# carcomputer_bottom2.net
KiCad netlist of a schematic drawn in EAGLE
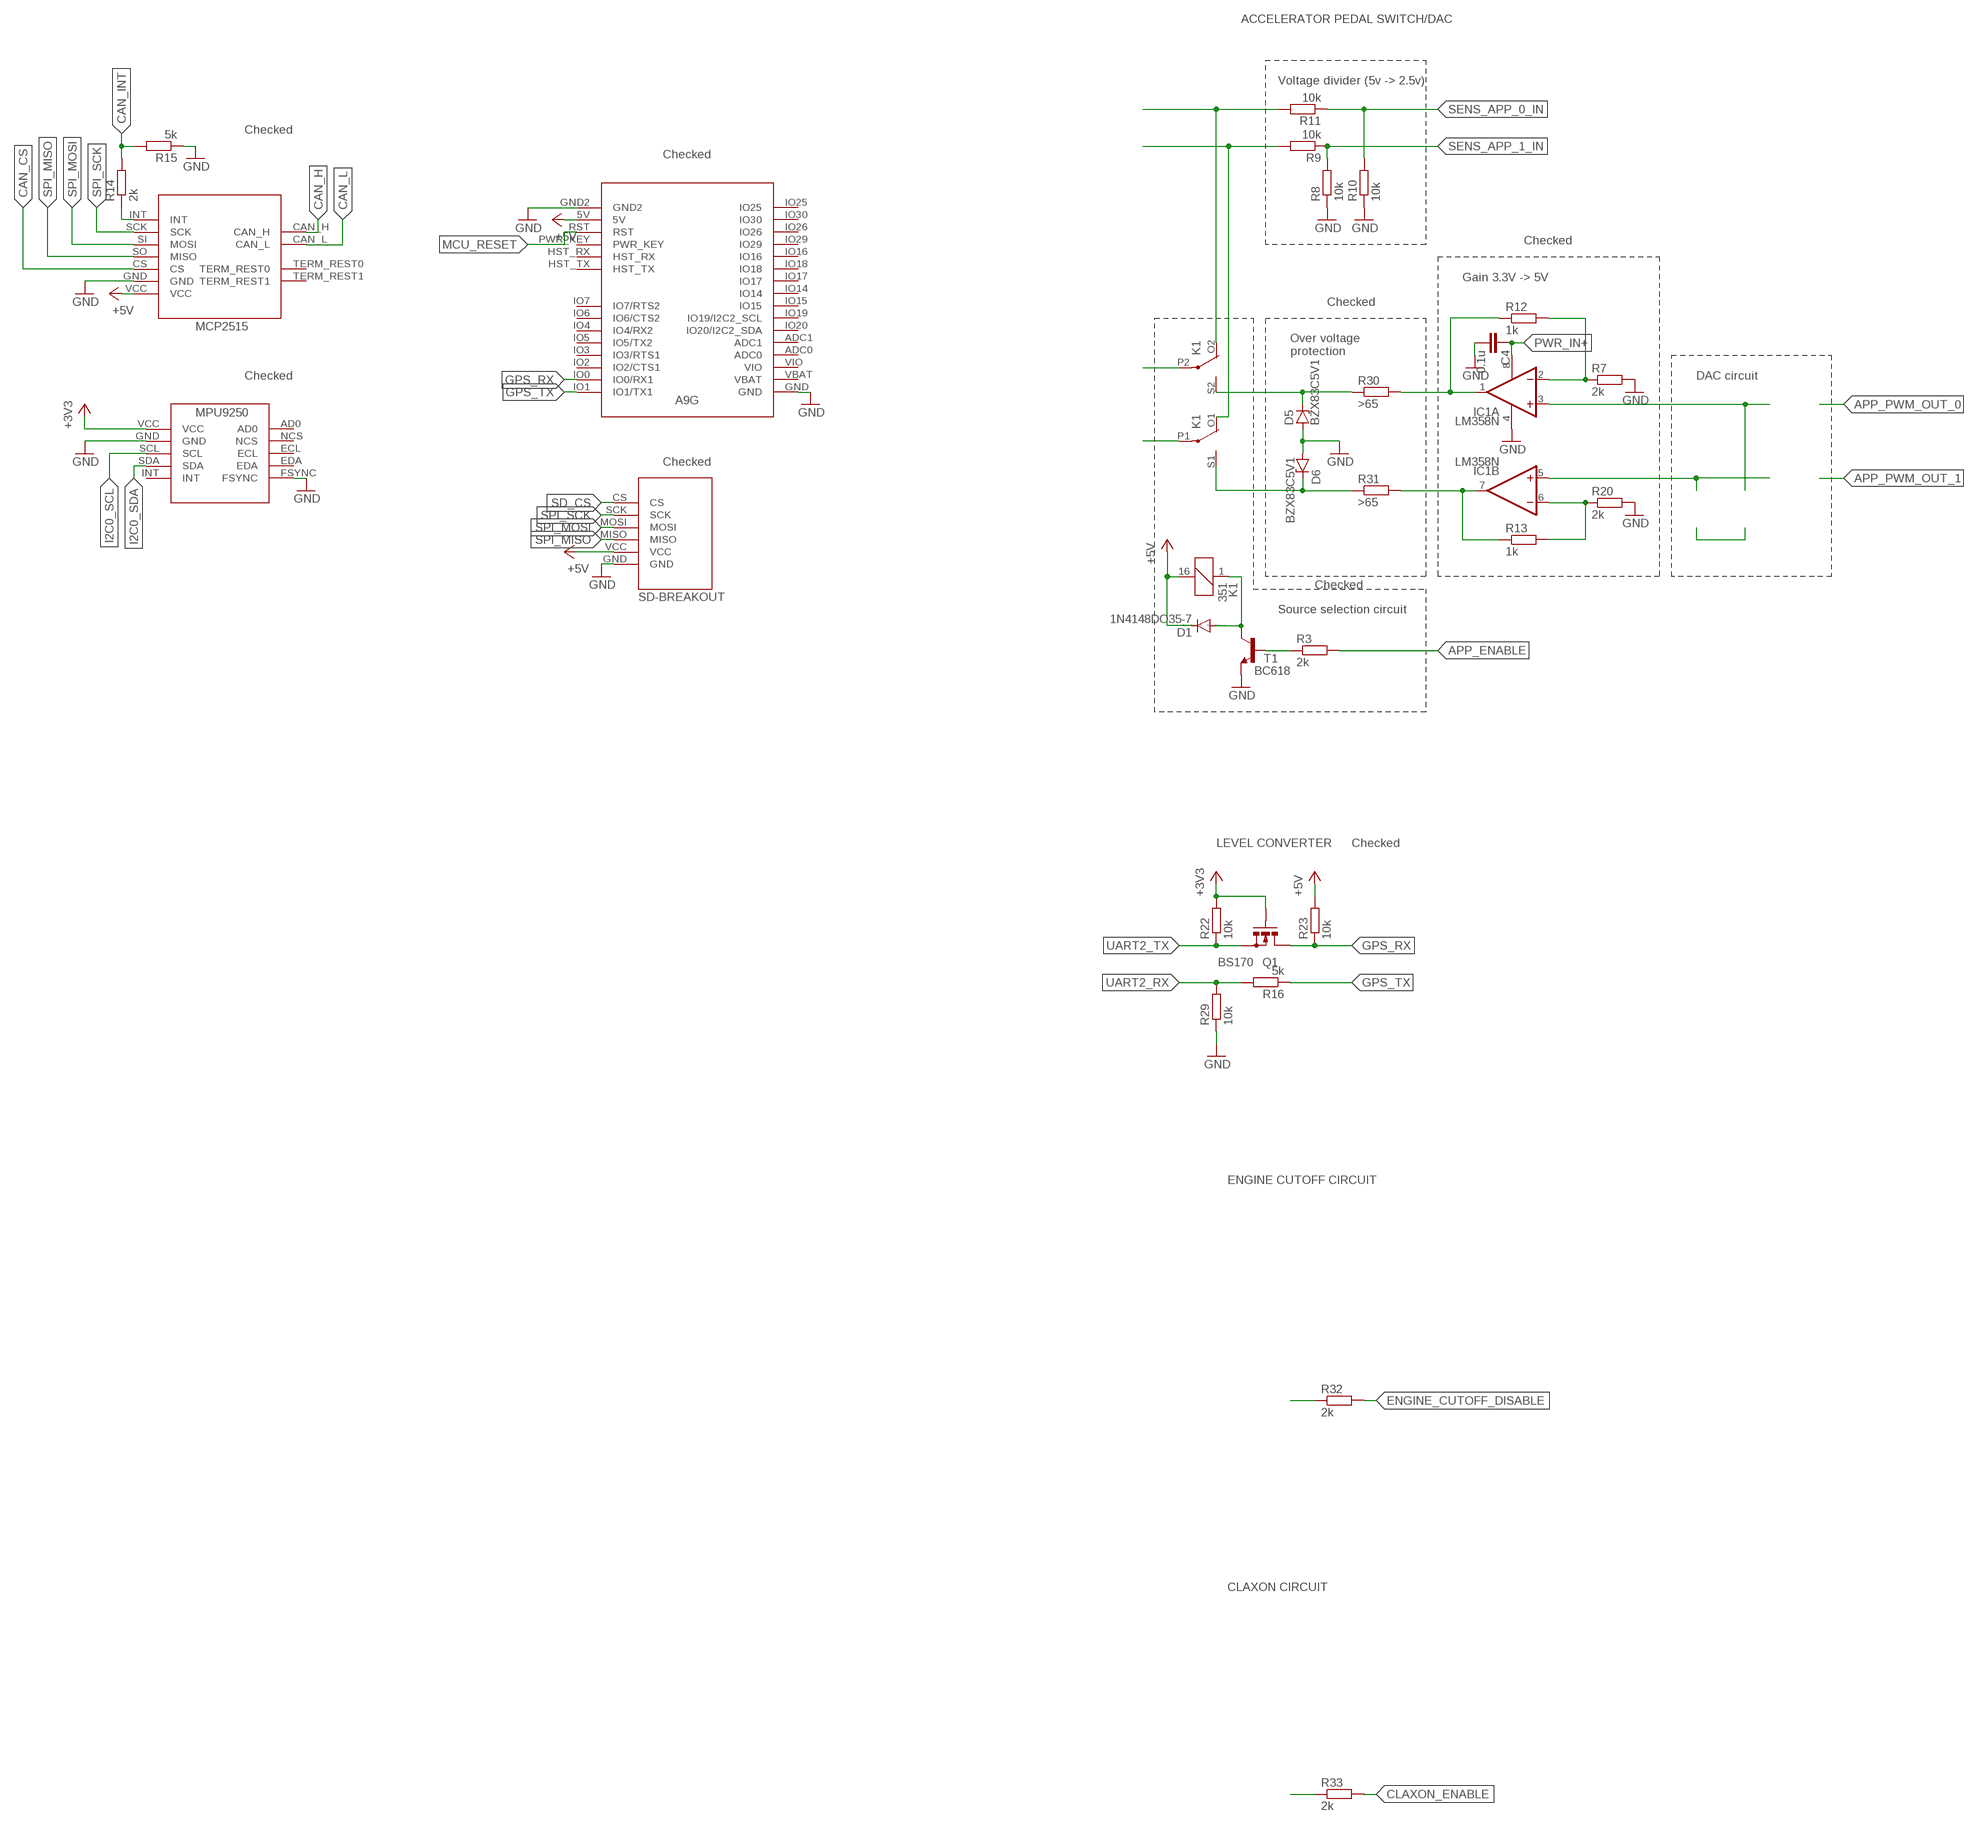
[diagram p0: schematic, sheet 1]

(export (version "E")
  (design (tool "Eeschema 10.0.6"))
  (components
    (comp (ref "C4")
      (value "0.1u")
      (footprint "eagle-import:C025-050X050")
      (libsource (lib "eagle-import") (part "C-EU025-050X050"))
    )
    (comp (ref "D1")
      (value "1N4148DO35-7")
      (footprint "eagle-import:DO35-7")
      (libsource (lib "eagle-import") (part "1N4148DO35-7"))
    )
    (comp (ref "D5")
      (value "BZX83C5V1")
      (footprint "eagle-import:DO41Z10")
      (libsource (lib "eagle-import") (part "BZX85"))
    )
    (comp (ref "D6")
      (value "BZX83C5V1")
      (footprint "eagle-import:DO41Z10")
      (libsource (lib "eagle-import") (part "BZX85"))
    )
    (comp (ref "IC1")
      (value "LM358N")
      (footprint "eagle-import:DIL08")
      (libsource (lib "eagle-import") (part "LM358N"))
    )
    (comp (ref "K1")
      (value "351")
      (footprint "eagle-import:351")
      (libsource (lib "eagle-import") (part "351"))
    )
    (comp (ref "Q1")
      (value "BS170")
      (footprint "eagle-import:SOT54E")
      (libsource (lib "eagle-import") (part "BS170"))
    )
    (comp (ref "R3")
      (value "2k")
      (footprint "eagle-import:0207_7")
      (libsource (lib "eagle-import") (part "R-EU_0207/7"))
    )
    (comp (ref "R7")
      (value "2k")
      (footprint "eagle-import:0207_7")
      (libsource (lib "eagle-import") (part "R-EU_0207/7"))
    )
    (comp (ref "R8")
      (value "10k")
      (footprint "eagle-import:0207_7")
      (libsource (lib "eagle-import") (part "R-EU_0207/7"))
    )
    (comp (ref "R9")
      (value "10k")
      (footprint "eagle-import:0207_7")
      (libsource (lib "eagle-import") (part "R-EU_0207/7"))
    )
    (comp (ref "R10")
      (value "10k")
      (footprint "eagle-import:0207_7")
      (libsource (lib "eagle-import") (part "R-EU_0207/7"))
    )
    (comp (ref "R11")
      (value "10k")
      (footprint "eagle-import:0207_7")
      (libsource (lib "eagle-import") (part "R-EU_0207/7"))
    )
    (comp (ref "R12")
      (value "1k")
      (footprint "eagle-import:0207_7")
      (libsource (lib "eagle-import") (part "R-EU_0207/7"))
    )
    (comp (ref "R13")
      (value "1k")
      (footprint "eagle-import:0207_7")
      (libsource (lib "eagle-import") (part "R-EU_0207/7"))
    )
    (comp (ref "R14")
      (value "2k")
      (footprint "eagle-import:0207_7")
      (libsource (lib "eagle-import") (part "R-EU_0207/7"))
    )
    (comp (ref "R15")
      (value "5k")
      (footprint "eagle-import:0207_7")
      (libsource (lib "eagle-import") (part "R-EU_0207/7"))
    )
    (comp (ref "R16")
      (value "5k")
      (footprint "eagle-import:0207_7")
      (libsource (lib "eagle-import") (part "R-EU_0207/7"))
    )
    (comp (ref "R20")
      (value "2k")
      (footprint "eagle-import:0207_7")
      (libsource (lib "eagle-import") (part "R-EU_0207/7"))
    )
    (comp (ref "R22")
      (value "10k")
      (footprint "eagle-import:0207_7")
      (libsource (lib "eagle-import") (part "R-EU_0207/7"))
    )
    (comp (ref "R23")
      (value "10k")
      (footprint "eagle-import:0207_7")
      (libsource (lib "eagle-import") (part "R-EU_0207/7"))
    )
    (comp (ref "R29")
      (value "10k")
      (footprint "eagle-import:0207_7")
      (libsource (lib "eagle-import") (part "R-EU_0207/7"))
    )
    (comp (ref "R30")
      (value ">65")
      (footprint "eagle-import:0207_7")
      (libsource (lib "eagle-import") (part "R-EU_0207/7"))
    )
    (comp (ref "R31")
      (value ">65")
      (footprint "eagle-import:0207_7")
      (libsource (lib "eagle-import") (part "R-EU_0207/7"))
    )
    (comp (ref "R32")
      (value "2k")
      (footprint "eagle-import:0207_7")
      (libsource (lib "eagle-import") (part "R-EU_0207/7"))
    )
    (comp (ref "R33")
      (value "2k")
      (footprint "eagle-import:0207_7")
      (libsource (lib "eagle-import") (part "R-EU_0207/7"))
    )
    (comp (ref "T1")
      (value "BC618")
      (footprint "eagle-import:TO92-EBC")
      (libsource (lib "eagle-import") (part "BC618"))
    )
    (comp (ref "U$2")
      (value "MCP2515_DEVBOARDINVERTED")
      (footprint "eagle-import:MCP2515_DEVBOARD_INVERTED")
      (libsource (lib "eagle-import") (part "MCP2515_DEVBOARDINVERTED"))
    )
    (comp (ref "U$3")
      (value "MPU9250_BREAKOUT")
      (footprint "eagle-import:MPU9250_BREAKOUT")
      (libsource (lib "eagle-import") (part "MPU9250_BREAKOUT"))
    )
    (comp (ref "U$5")
      (value "HKD-MICRO-SD-BREAKOUT")
      (footprint "eagle-import:HKD-MICRO-SD-BREAKOUT")
      (libsource (lib "eagle-import") (part "HKD-MICRO-SD-BREAKOUT"))
    )
    (comp (ref "U$6")
      (value "A9G")
      (footprint "eagle-import:A9G")
      (libsource (lib "eagle-import") (part "A9G"))
    )
  )
  (nets
    (net (code "1") (name "+3V3") (class "Default")
      (node (ref "Q1") (pin "G") (pinfunction "G_G") (pintype "passive"))
      (node (ref "R22") (pin "2") (pinfunction "2_2") (pintype "passive"))
      (node (ref "U$3") (pin "VCC") (pinfunction "VCC_VCC") (pintype "bidirectional"))
    )
    (net (code "2") (name "+5V") (class "Default")
      (node (ref "D1") (pin "C") (pinfunction "C_C") (pintype "passive"))
      (node (ref "K1") (pin "16") (pinfunction "2_16") (pintype "passive"))
      (node (ref "R23") (pin "2") (pinfunction "2_2") (pintype "passive"))
      (node (ref "U$2") (pin "VCC") (pinfunction "VCC_VCC") (pintype "bidirectional"))
      (node (ref "U$5") (pin "VCC") (pinfunction "VCC_VCC") (pintype "bidirectional"))
      (node (ref "U$6") (pin "5V") (pinfunction "5V_5V") (pintype "bidirectional"))
    )
    (net (code "3") (name "APP_ENABLE") (class "Default")
      (node (ref "R3") (pin "2") (pinfunction "2_2") (pintype "passive"))
    )
    (net (code "6") (name "CAN_CS") (class "Default")
      (node (ref "U$2") (pin "CS") (pinfunction "CS_CS") (pintype "input"))
    )
    (net (code "7") (name "CAN_H") (class "Default")
      (node (ref "U$2") (pin "CAN_H") (pinfunction "CAN_H_CAN_H") (pintype "bidirectional"))
    )
    (net (code "8") (name "CAN_INT") (class "Default")
      (node (ref "R14") (pin "2") (pinfunction "2_2") (pintype "passive"))
      (node (ref "R15") (pin "2") (pinfunction "2_2") (pintype "passive"))
    )
    (net (code "9") (name "CAN_L") (class "Default")
      (node (ref "U$2") (pin "CAN_L") (pinfunction "CAN_L_CAN_L") (pintype "bidirectional"))
    )
    (net (code "10") (name "CLAXON_ENABLE") (class "Default")
      (node (ref "R33") (pin "2") (pinfunction "2_2") (pintype "passive"))
    )
    (net (code "11") (name "ENGINE_CUTOFF_DISABLE") (class "Default")
      (node (ref "R32") (pin "2") (pinfunction "2_2") (pintype "passive"))
    )
    (net (code "12") (name "GND") (class "Default")
      (node (ref "C4") (pin "2") (pinfunction "2_2") (pintype "passive"))
      (node (ref "D5") (pin "A") (pinfunction "A_A") (pintype "passive"))
      (node (ref "D6") (pin "A") (pinfunction "A_A") (pintype "passive"))
      (node (ref "IC1") (pin "4") (pinfunction "V-_4") (pintype "power_in"))
      (node (ref "R10") (pin "1") (pinfunction "1_1") (pintype "passive"))
      (node (ref "R15") (pin "1") (pinfunction "1_1") (pintype "passive"))
      (node (ref "R20") (pin "2") (pinfunction "2_2") (pintype "passive"))
      (node (ref "R29") (pin "1") (pinfunction "1_1") (pintype "passive"))
      (node (ref "R7") (pin "2") (pinfunction "2_2") (pintype "passive"))
      (node (ref "R8") (pin "1") (pinfunction "1_1") (pintype "passive"))
      (node (ref "T1") (pin "E") (pinfunction "E_E") (pintype "passive"))
      (node (ref "U$2") (pin "GND") (pinfunction "GND_GND") (pintype "bidirectional"))
      (node (ref "U$3") (pin "FSYNC") (pinfunction "FSYNC_FSYNC") (pintype "bidirectional"))
      (node (ref "U$3") (pin "GND") (pinfunction "GND_GND") (pintype "bidirectional"))
      (node (ref "U$5") (pin "GND") (pinfunction "GND_GND") (pintype "bidirectional"))
      (node (ref "U$6") (pin "GND") (pinfunction "GND_GND") (pintype "bidirectional"))
      (node (ref "U$6") (pin "GND2") (pinfunction "GND2_GND2") (pintype "bidirectional"))
    )
    (net (code "13") (name "GPS_RX") (class "Default")
      (node (ref "Q1") (pin "D") (pinfunction "D_D") (pintype "passive"))
      (node (ref "R23") (pin "1") (pinfunction "1_1") (pintype "passive"))
      (node (ref "U$6") (pin "IO0") (pinfunction "IO0/RX1_IO0") (pintype "bidirectional"))
    )
    (net (code "14") (name "GPS_TX") (class "Default")
      (node (ref "R16") (pin "1") (pinfunction "1_1") (pintype "passive"))
      (node (ref "U$6") (pin "IO1") (pinfunction "IO1/TX1_IO1") (pintype "bidirectional"))
    )
    (net (code "15") (name "I2C0_SCL") (class "Default")
      (node (ref "U$3") (pin "SCL") (pinfunction "SCL_SCL") (pintype "bidirectional"))
    )
    (net (code "16") (name "I2C0_SDA") (class "Default")
      (node (ref "U$3") (pin "SDA") (pinfunction "SDA_SDA") (pintype "bidirectional"))
    )
    (net (code "17") (name "MCU_RESET") (class "Default")
      (node (ref "U$6") (pin "RST") (pinfunction "RST_RST") (pintype "bidirectional"))
    )
    (net (code "18") (name "Net-(D1-PadA)") (class "Default")
      (node (ref "D1") (pin "A") (pinfunction "A_A") (pintype "passive"))
      (node (ref "K1") (pin "1") (pinfunction "1_1") (pintype "passive"))
      (node (ref "T1") (pin "C") (pinfunction "C_C") (pintype "passive"))
    )
    (net (code "19") (name "Net-(IC1A--IN)") (class "Default")
      (node (ref "IC1") (pin "2") (pinfunction "-IN_2") (pintype "input"))
      (node (ref "R12") (pin "2") (pinfunction "2_2") (pintype "passive"))
      (node (ref "R7") (pin "1") (pinfunction "1_1") (pintype "passive"))
    )
    (net (code "20") (name "Net-(IC1A-OUT)") (class "Default")
      (node (ref "IC1") (pin "1") (pinfunction "OUT_1") (pintype "output"))
      (node (ref "R12") (pin "1") (pinfunction "1_1") (pintype "passive"))
      (node (ref "R30") (pin "2") (pinfunction "2_2") (pintype "passive"))
    )
    (net (code "21") (name "Net-(IC1B--IN)") (class "Default")
      (node (ref "IC1") (pin "6") (pinfunction "-IN_6") (pintype "input"))
      (node (ref "R13") (pin "2") (pinfunction "2_2") (pintype "passive"))
      (node (ref "R20") (pin "1") (pinfunction "1_1") (pintype "passive"))
    )
    (net (code "22") (name "Net-(IC1B-OUT)") (class "Default")
      (node (ref "IC1") (pin "7") (pinfunction "OUT_7") (pintype "output"))
      (node (ref "R13") (pin "1") (pinfunction "1_1") (pintype "passive"))
      (node (ref "R31") (pin "2") (pinfunction "2_2") (pintype "passive"))
    )
    (net (code "23") (name "Net-(K1B-O)") (class "Default")
      (node (ref "K1") (pin "O1") (pinfunction "O_O1") (pintype "passive"))
      (node (ref "R9") (pin "2") (pinfunction "2_2") (pintype "passive"))
    )
    (net (code "24") (name "Net-(K1B-S)") (class "Default")
      (node (ref "D6") (pin "C") (pinfunction "C_C") (pintype "passive"))
      (node (ref "K1") (pin "S1") (pinfunction "S_S1") (pintype "passive"))
      (node (ref "R31") (pin "1") (pinfunction "1_1") (pintype "passive"))
    )
    (net (code "25") (name "Net-(K1C-O)") (class "Default")
      (node (ref "K1") (pin "O2") (pinfunction "O_O2") (pintype "passive"))
      (node (ref "R11") (pin "2") (pinfunction "2_2") (pintype "passive"))
    )
    (net (code "26") (name "Net-(K1C-S)") (class "Default")
      (node (ref "D5") (pin "C") (pinfunction "C_C") (pintype "passive"))
      (node (ref "K1") (pin "S2") (pinfunction "S_S2") (pintype "passive"))
      (node (ref "R30") (pin "1") (pinfunction "1_1") (pintype "passive"))
    )
    (net (code "27") (name "Net-(R3-Pad1)") (class "Default")
      (node (ref "R3") (pin "1") (pinfunction "1_1") (pintype "passive"))
      (node (ref "T1") (pin "B") (pinfunction "B_B") (pintype "passive"))
    )
    (net (code "28") (name "Net-(R14-Pad1)") (class "Default")
      (node (ref "R14") (pin "1") (pinfunction "1_1") (pintype "passive"))
      (node (ref "U$2") (pin "INT") (pinfunction "INT_INT") (pintype "output"))
    )
    (net (code "29") (name "PWR_IN+") (class "Default")
      (node (ref "C4") (pin "1") (pinfunction "1_1") (pintype "passive"))
      (node (ref "IC1") (pin "8") (pinfunction "V+_8") (pintype "power_in"))
    )
    (net (code "30") (name "SD_CS") (class "Default")
      (node (ref "U$5") (pin "CS") (pinfunction "CS_CS") (pintype "bidirectional"))
    )
    (net (code "31") (name "SENS_APP_0_IN") (class "Default")
      (node (ref "R10") (pin "2") (pinfunction "2_2") (pintype "passive"))
      (node (ref "R11") (pin "1") (pinfunction "1_1") (pintype "passive"))
    )
    (net (code "32") (name "SENS_APP_1_IN") (class "Default")
      (node (ref "R8") (pin "2") (pinfunction "2_2") (pintype "passive"))
      (node (ref "R9") (pin "1") (pinfunction "1_1") (pintype "passive"))
    )
    (net (code "33") (name "SPI_MISO") (class "Default")
      (node (ref "U$2") (pin "SO") (pinfunction "MISO_SO") (pintype "output"))
      (node (ref "U$5") (pin "MISO") (pinfunction "MISO_MISO") (pintype "bidirectional"))
    )
    (net (code "34") (name "SPI_MOSI") (class "Default")
      (node (ref "U$2") (pin "SI") (pinfunction "MOSI_SI") (pintype "input"))
      (node (ref "U$5") (pin "MOSI") (pinfunction "MOSI_MOSI") (pintype "bidirectional"))
    )
    (net (code "35") (name "SPI_SCK") (class "Default")
      (node (ref "U$2") (pin "SCK") (pinfunction "SCK_SCK") (pintype "input"))
      (node (ref "U$5") (pin "SCK") (pinfunction "SCK_SCK") (pintype "bidirectional"))
    )
    (net (code "36") (name "UART2_RX") (class "Default")
      (node (ref "R16") (pin "2") (pinfunction "2_2") (pintype "passive"))
      (node (ref "R29") (pin "2") (pinfunction "2_2") (pintype "passive"))
    )
    (net (code "37") (name "UART2_TX") (class "Default")
      (node (ref "Q1") (pin "S") (pinfunction "S_S") (pintype "passive"))
      (node (ref "R22") (pin "1") (pinfunction "1_1") (pintype "passive"))
    )
    (net (code "38") (name "unconnected-(IC1A-+IN-Pad3)") (class "Default")
      (node (ref "IC1") (pin "3") (pinfunction "+IN_3") (pintype "input"))
    )
    (net (code "39") (name "unconnected-(IC1B-+IN-Pad5)") (class "Default")
      (node (ref "IC1") (pin "5") (pinfunction "+IN_5") (pintype "input"))
    )
    (net (code "40") (name "unconnected-(K1B-P-PadP1)") (class "Default")
      (node (ref "K1") (pin "P1") (pinfunction "P_P1") (pintype "passive"))
    )
    (net (code "41") (name "unconnected-(K1C-P-PadP2)") (class "Default")
      (node (ref "K1") (pin "P2") (pinfunction "P_P2") (pintype "passive"))
    )
    (net (code "42") (name "unconnected-(R32-Pad1)") (class "Default")
      (node (ref "R32") (pin "1") (pinfunction "1_1") (pintype "passive"))
    )
    (net (code "43") (name "unconnected-(R33-Pad1)") (class "Default")
      (node (ref "R33") (pin "1") (pinfunction "1_1") (pintype "passive"))
    )
    (net (code "44") (name "unconnected-(U$2-PadTERM_REST0)") (class "Default")
      (node (ref "U$2") (pin "TERM_REST0") (pinfunction "TERM_REST0_TERM_REST0") (pintype "bidirectional"))
    )
    (net (code "45") (name "unconnected-(U$2-PadTERM_REST1)") (class "Default")
      (node (ref "U$2") (pin "TERM_REST1") (pinfunction "TERM_REST1_TERM_REST1") (pintype "bidirectional"))
    )
    (net (code "46") (name "unconnected-(U$3-PadAD0)") (class "Default")
      (node (ref "U$3") (pin "AD0") (pinfunction "AD0_AD0") (pintype "bidirectional"))
    )
    (net (code "47") (name "unconnected-(U$3-PadECL)") (class "Default")
      (node (ref "U$3") (pin "ECL") (pinfunction "ECL_ECL") (pintype "bidirectional"))
    )
    (net (code "48") (name "unconnected-(U$3-PadEDA)") (class "Default")
      (node (ref "U$3") (pin "EDA") (pinfunction "EDA_EDA") (pintype "bidirectional"))
    )
    (net (code "49") (name "unconnected-(U$3-PadINT)") (class "Default")
      (node (ref "U$3") (pin "INT") (pinfunction "INT_INT") (pintype "bidirectional"))
    )
    (net (code "50") (name "unconnected-(U$3-PadNCS)") (class "Default")
      (node (ref "U$3") (pin "NCS") (pinfunction "NCS_NCS") (pintype "bidirectional"))
    )
    (net (code "51") (name "unconnected-(U$6-IO2{slash}CTS1-PadIO2)") (class "Default")
      (node (ref "U$6") (pin "IO2") (pinfunction "IO2/CTS1_IO2") (pintype "bidirectional"))
    )
    (net (code "52") (name "unconnected-(U$6-IO3{slash}RTS1-PadIO3)") (class "Default")
      (node (ref "U$6") (pin "IO3") (pinfunction "IO3/RTS1_IO3") (pintype "bidirectional"))
    )
    (net (code "53") (name "unconnected-(U$6-IO4{slash}RX2-PadIO4)") (class "Default")
      (node (ref "U$6") (pin "IO4") (pinfunction "IO4/RX2_IO4") (pintype "bidirectional"))
    )
    (net (code "54") (name "unconnected-(U$6-IO5{slash}TX2-PadIO5)") (class "Default")
      (node (ref "U$6") (pin "IO5") (pinfunction "IO5/TX2_IO5") (pintype "bidirectional"))
    )
    (net (code "55") (name "unconnected-(U$6-IO6{slash}CTS2-PadIO6)") (class "Default")
      (node (ref "U$6") (pin "IO6") (pinfunction "IO6/CTS2_IO6") (pintype "bidirectional"))
    )
    (net (code "56") (name "unconnected-(U$6-IO7{slash}RTS2-PadIO7)") (class "Default")
      (node (ref "U$6") (pin "IO7") (pinfunction "IO7/RTS2_IO7") (pintype "bidirectional"))
    )
    (net (code "57") (name "unconnected-(U$6-IO19{slash}I2C2_SCL-PadIO19)") (class "Default")
      (node (ref "U$6") (pin "IO19") (pinfunction "IO19/I2C2_SCL_IO19") (pintype "bidirectional"))
    )
    (net (code "58") (name "unconnected-(U$6-IO20{slash}I2C2_SDA-PadIO20)") (class "Default")
      (node (ref "U$6") (pin "IO20") (pinfunction "IO20/I2C2_SDA_IO20") (pintype "bidirectional"))
    )
    (net (code "59") (name "unconnected-(U$6-PadADC0)") (class "Default")
      (node (ref "U$6") (pin "ADC0") (pinfunction "ADC0_ADC0") (pintype "bidirectional"))
    )
    (net (code "60") (name "unconnected-(U$6-PadADC1)") (class "Default")
      (node (ref "U$6") (pin "ADC1") (pinfunction "ADC1_ADC1") (pintype "bidirectional"))
    )
    (net (code "61") (name "unconnected-(U$6-PadHST_RX)") (class "Default")
      (node (ref "U$6") (pin "HST_RX") (pinfunction "HST_RX_HST_RX") (pintype "bidirectional"))
    )
    (net (code "62") (name "unconnected-(U$6-PadHST_TX)") (class "Default")
      (node (ref "U$6") (pin "HST_TX") (pinfunction "HST_TX_HST_TX") (pintype "bidirectional"))
    )
    (net (code "63") (name "unconnected-(U$6-PadIO14)") (class "Default")
      (node (ref "U$6") (pin "IO14") (pinfunction "IO14_IO14") (pintype "bidirectional"))
    )
    (net (code "64") (name "unconnected-(U$6-PadIO15)") (class "Default")
      (node (ref "U$6") (pin "IO15") (pinfunction "IO15_IO15") (pintype "bidirectional"))
    )
    (net (code "65") (name "unconnected-(U$6-PadIO16)") (class "Default")
      (node (ref "U$6") (pin "IO16") (pinfunction "IO16_IO16") (pintype "bidirectional"))
    )
    (net (code "66") (name "unconnected-(U$6-PadIO17)") (class "Default")
      (node (ref "U$6") (pin "IO17") (pinfunction "IO17_IO17") (pintype "bidirectional"))
    )
    (net (code "67") (name "unconnected-(U$6-PadIO18)") (class "Default")
      (node (ref "U$6") (pin "IO18") (pinfunction "IO18_IO18") (pintype "bidirectional"))
    )
    (net (code "68") (name "unconnected-(U$6-PadIO25)") (class "Default")
      (node (ref "U$6") (pin "IO25") (pinfunction "IO25_IO25") (pintype "bidirectional"))
    )
    (net (code "69") (name "unconnected-(U$6-PadIO26)") (class "Default")
      (node (ref "U$6") (pin "IO26") (pinfunction "IO26_IO26") (pintype "bidirectional"))
    )
    (net (code "70") (name "unconnected-(U$6-PadIO29)") (class "Default")
      (node (ref "U$6") (pin "IO29") (pinfunction "IO29_IO29") (pintype "bidirectional"))
    )
    (net (code "71") (name "unconnected-(U$6-PadIO30)") (class "Default")
      (node (ref "U$6") (pin "IO30") (pinfunction "IO30_IO30") (pintype "bidirectional"))
    )
    (net (code "72") (name "unconnected-(U$6-PadPWR_KEY)") (class "Default")
      (node (ref "U$6") (pin "PWR_KEY") (pinfunction "PWR_KEY_PWR_KEY") (pintype "bidirectional"))
    )
    (net (code "73") (name "unconnected-(U$6-PadVBAT)") (class "Default")
      (node (ref "U$6") (pin "VBAT") (pinfunction "VBAT_VBAT") (pintype "bidirectional"))
    )
    (net (code "74") (name "unconnected-(U$6-PadVIO)") (class "Default")
      (node (ref "U$6") (pin "VIO") (pinfunction "VIO_VIO") (pintype "bidirectional"))
    )
  )
)
